# paddles.net
KiCad netlist of a schematic drawn in Altium Designer
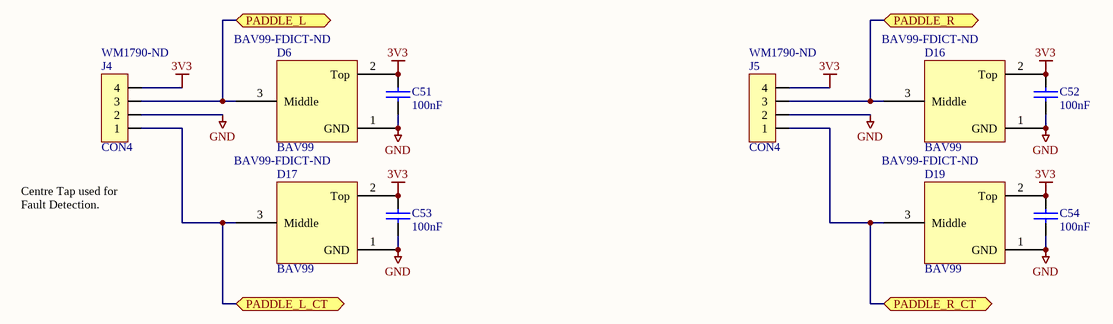
[diagram p0: paddles.SchDoc]

(export (version "E")
  (design (tool "Eeschema 10.0.6"))
  (components
    (comp (ref "C51")
      (value "100nF")
      (footprint "0603")
      (description "Capacitor")
      (libsource (lib "*") (part "CAP"))
    )
    (comp (ref "C52")
      (value "100nF")
      (footprint "0603")
      (description "Capacitor")
      (libsource (lib "*") (part "CAP"))
    )
    (comp (ref "C53")
      (value "100nF")
      (footprint "0603")
      (description "Capacitor")
      (libsource (lib "*") (part "CAP"))
    )
    (comp (ref "C54")
      (value "100nF")
      (footprint "0603")
      (description "Capacitor")
      (libsource (lib "*") (part "CAP"))
    )
    (comp (ref "D6")
      (value "BAV99")
      (footprint "SOT23-3")
      (description "Dual Diode")
      (fields
        (field (name "SUPPLIER PART NUMBER 1") "BAV99-FDICT-ND")
        (field (name "MANUFACTURER") "Diodes Inc")
        (field (name "MANUFACTURER PART NUMBER") "BAV99-7-F")
      )
      (libsource (lib "Miscellaneous") (part "BAV99"))
    )
    (comp (ref "D16")
      (value "BAV99")
      (footprint "SOT23-3")
      (description "Dual Diode")
      (fields
        (field (name "SUPPLIER PART NUMBER 1") "BAV99-FDICT-ND")
        (field (name "MANUFACTURER") "Diodes Inc")
        (field (name "MANUFACTURER PART NUMBER") "BAV99-7-F")
      )
      (libsource (lib "Miscellaneous") (part "BAV99"))
    )
    (comp (ref "D17")
      (value "BAV99")
      (footprint "SOT23-3")
      (description "Dual Diode")
      (fields
        (field (name "SUPPLIER PART NUMBER 1") "BAV99-FDICT-ND")
        (field (name "MANUFACTURER") "Diodes Inc")
        (field (name "MANUFACTURER PART NUMBER") "BAV99-7-F")
      )
      (libsource (lib "Miscellaneous") (part "BAV99"))
    )
    (comp (ref "D19")
      (value "BAV99")
      (footprint "SOT23-3")
      (description "Dual Diode")
      (fields
        (field (name "SUPPLIER PART NUMBER 1") "BAV99-FDICT-ND")
        (field (name "MANUFACTURER") "Diodes Inc")
        (field (name "MANUFACTURER PART NUMBER") "BAV99-7-F")
      )
      (libsource (lib "Miscellaneous") (part "BAV99"))
    )
    (comp (ref "J4")
      (value "CON4")
      (footprint "MICROFIT-4-VERT")
      (description "Connector")
      (fields
        (field (name "SUPPLIER PART NUMBER 1") "WM1790-ND")
        (field (name "MANUFACTURER") "Molex Inc")
        (field (name "MANUFACTURER PART NUMBER") "0430450412")
      )
      (libsource (lib "Connectors") (part "CON4"))
    )
    (comp (ref "J5")
      (value "CON4")
      (footprint "MICROFIT-4-VERT")
      (description "Connector")
      (fields
        (field (name "SUPPLIER PART NUMBER 1") "WM1790-ND")
        (field (name "MANUFACTURER") "Molex Inc")
        (field (name "MANUFACTURER PART NUMBER") "0430450412")
      )
      (libsource (lib "Connectors") (part "CON4"))
    )
  )
  (nets
    (net (code "1") (name "/PADDLE_L") (class "Default")
      (node (ref "D6") (pin "3") (pinfunction "Middle_3") (pintype "passive"))
      (node (ref "J4") (pin "3") (pinfunction "3_3") (pintype "passive"))
    )
    (net (code "2") (name "/PADDLE_L_CT") (class "Default")
      (node (ref "D17") (pin "3") (pinfunction "Middle_3") (pintype "passive"))
      (node (ref "J4") (pin "1") (pinfunction "1_1") (pintype "passive"))
    )
    (net (code "3") (name "/PADDLE_R") (class "Default")
      (node (ref "D16") (pin "3") (pinfunction "Middle_3") (pintype "passive"))
      (node (ref "J5") (pin "3") (pinfunction "3_3") (pintype "passive"))
    )
    (net (code "4") (name "/PADDLE_R_CT") (class "Default")
      (node (ref "D19") (pin "3") (pinfunction "Middle_3") (pintype "passive"))
      (node (ref "J5") (pin "1") (pinfunction "1_1") (pintype "passive"))
    )
    (net (code "5") (name "3V3") (class "Default")
      (node (ref "C51") (pin "1") (pinfunction "1_1") (pintype "passive"))
      (node (ref "C52") (pin "1") (pinfunction "1_1") (pintype "passive"))
      (node (ref "C53") (pin "1") (pinfunction "1_1") (pintype "passive"))
      (node (ref "C54") (pin "1") (pinfunction "1_1") (pintype "passive"))
      (node (ref "D16") (pin "2") (pinfunction "Top_2") (pintype "passive"))
      (node (ref "D17") (pin "2") (pinfunction "Top_2") (pintype "passive"))
      (node (ref "D19") (pin "2") (pinfunction "Top_2") (pintype "passive"))
      (node (ref "D6") (pin "2") (pinfunction "Top_2") (pintype "passive"))
      (node (ref "J4") (pin "4") (pinfunction "4_4") (pintype "passive"))
      (node (ref "J5") (pin "4") (pinfunction "4_4") (pintype "passive"))
    )
    (net (code "6") (name "GND") (class "Default")
      (node (ref "C51") (pin "2") (pinfunction "2_2") (pintype "passive"))
      (node (ref "C52") (pin "2") (pinfunction "2_2") (pintype "passive"))
      (node (ref "C53") (pin "2") (pinfunction "2_2") (pintype "passive"))
      (node (ref "C54") (pin "2") (pinfunction "2_2") (pintype "passive"))
      (node (ref "D16") (pin "1") (pinfunction "GND_1") (pintype "passive"))
      (node (ref "D17") (pin "1") (pinfunction "GND_1") (pintype "passive"))
      (node (ref "D19") (pin "1") (pinfunction "GND_1") (pintype "passive"))
      (node (ref "D6") (pin "1") (pinfunction "GND_1") (pintype "passive"))
      (node (ref "J4") (pin "2") (pinfunction "2_2") (pintype "passive"))
      (node (ref "J5") (pin "2") (pinfunction "2_2") (pintype "passive"))
    )
  )
)
